# LEDS.net
KiCad netlist of a schematic drawn in Altium Designer
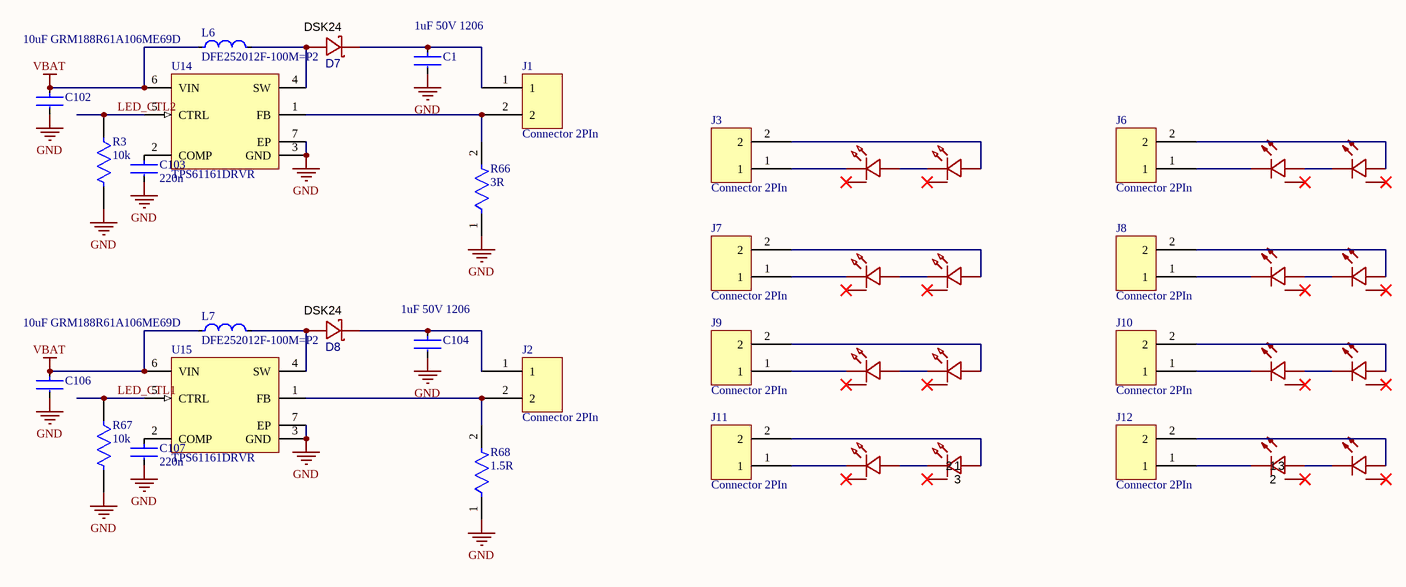
[diagram p0: LEDS.SchDoc]

(export (version "E")
  (design (tool "Eeschema 10.0.6"))
  (components
    (comp (ref "C1")
      (value "1uF 50V 1206")
      (footprint "FP-1206-L_3_2_0_2-W_1_6_0-IPC_B")
      (description "C1848")
      (fields (field (name "TOLERANCE") "5%"))
      (libsource (lib "LEAKCAM") (part "CMP-04427-010925-1"))
    )
    (comp (ref "C102")
      (value "10uF GRM188R61A106ME69D")
      (footprint "FP-GRM188-0_15-MFG")
      (description "C19702")
      (fields (field (name "TOLERANCE") "20%"))
      (libsource (lib "LEAKCAM") (part "CMP-06035-003612-1"))
    )
    (comp (ref "C103")
      (value "220n")
      (footprint "CAP_0402")
      (description "C16772")
      (fields (field (name "TOLERANCE") "10%"))
      (libsource (lib "LEAKCAM") (part "CMP-03422-001116-1"))
    )
    (comp (ref "C104")
      (value "1uF 50V 1206")
      (footprint "FP-1206-L_3_2_0_2-W_1_6_0-IPC_B")
      (description "C1848")
      (fields (field (name "TOLERANCE") "5%"))
      (libsource (lib "LEAKCAM") (part "CMP-04427-010925-1"))
    )
    (comp (ref "C106")
      (value "10uF GRM188R61A106ME69D")
      (footprint "FP-GRM188-0_15-MFG")
      (description "C19702")
      (fields (field (name "TOLERANCE") "20%"))
      (libsource (lib "LEAKCAM") (part "CMP-06035-003612-1"))
    )
    (comp (ref "C107")
      (value "220n")
      (footprint "CAP_0402")
      (description "C16772")
      (fields (field (name "TOLERANCE") "10%"))
      (libsource (lib "LEAKCAM") (part "CMP-03422-001116-1"))
    )
    (comp (ref "D7")
      (value "DSK24")
      (footprint "DSK24")
      (description "C22466352")
      (fields (field (name "MANUFACTURER") "MDD(辰达半导体)"))
      (libsource (lib "LEAKCAM") (part "dsk24_c64890"))
    )
    (comp (ref "D8")
      (value "DSK24")
      (footprint "DSK24")
      (description "C22466352")
      (fields (field (name "MANUFACTURER") "MDD(辰达半导体)"))
      (libsource (lib "LEAKCAM") (part "dsk24_c64890"))
    )
    (comp (ref "J1") (value "Connector 2PIn") (footprint "CON_2P") (libsource (lib "") (part "CON2P_1")))
    (comp (ref "J2") (value "Connector 2PIn") (footprint "CON_2P") (libsource (lib "") (part "CON2P_1")))
    (comp (ref "J3") (value "Connector 2PIn") (footprint "CON_2P") (libsource (lib "LEAKCAM") (part "CON2P")))
    (comp (ref "J6") (value "Connector 2PIn") (footprint "CON_2P") (libsource (lib "LEAKCAM") (part "CON2P")))
    (comp (ref "J7") (value "Connector 2PIn") (footprint "CON_2P") (libsource (lib "LEAKCAM") (part "CON2P")))
    (comp (ref "J8") (value "Connector 2PIn") (footprint "CON_2P") (libsource (lib "LEAKCAM") (part "CON2P")))
    (comp (ref "J9") (value "Connector 2PIn") (footprint "CON_2P") (libsource (lib "LEAKCAM") (part "CON2P")))
    (comp (ref "J10")
      (value "Connector 2PIn")
      (footprint "CON_2P")
      (libsource (lib "LEAKCAM") (part "CON2P"))
    )
    (comp (ref "J11")
      (value "Connector 2PIn")
      (footprint "CON_2P")
      (libsource (lib "LEAKCAM") (part "CON2P"))
    )
    (comp (ref "J12")
      (value "Connector 2PIn")
      (footprint "CON_2P")
      (libsource (lib "LEAKCAM") (part "CON2P"))
    )
    (comp (ref "L6")
      (value "DFE252012F-100M=P2")
      (footprint "FP-DFE252012C-IPC_B")
      (description "C703141")
      (fields (field (name "TOLERANCE") "20%"))
      (libsource (lib "LEAKCAM") (part "CMP-06042-007232-1"))
    )
    (comp (ref "L7")
      (value "DFE252012F-100M=P2")
      (footprint "FP-DFE252012C-IPC_B")
      (description "C703141")
      (fields (field (name "TOLERANCE") "20%"))
      (libsource (lib "LEAKCAM") (part "CMP-06042-007232-1"))
    )
    (comp (ref "LED1")
      (value "xl-hd3535uwc-a2")
      (footprint "XL-HD3535UWC-A2")
      (description "C3646951")
      (fields
        (field (name "MANUFACTURER") "XINGLIGHT(成兴光)")
        (field (name "MANUFACTURERPART") "XL-HD3535UWC-A2")
      )
      (libsource (lib "LEAKCAM") (part "xl-hd3535uwc-a2"))
    )
    (comp (ref "LED2")
      (value "xl-hd3535uwc-a2")
      (footprint "XL-HD3535UWC-A2")
      (description "C3646951")
      (fields
        (field (name "MANUFACTURER") "XINGLIGHT(成兴光)")
        (field (name "MANUFACTURERPART") "XL-HD3535UWC-A2")
      )
      (libsource (lib "LEAKCAM") (part "xl-hd3535uwc-a2"))
    )
    (comp (ref "LED3")
      (value "jnj-ltji0112w120/35mil/845-860nm")
      (footprint "JNJ-LTJI0112W120")
      (description "C19185834")
      (fields
        (field (name "MANUFACTURER") "JNJOPTO(强生光电)")
        (field (name "MANUFACTURERPART") "JNJ-LTJI0112W120/35mil/845-860nm")
      )
      (libsource (lib "LEAKCAM") (part "jnj-ltji0112w120/35mil/845-860nm"))
    )
    (comp (ref "LED4")
      (value "xl-hd3535uwc-a2")
      (footprint "XL-HD3535UWC-A2")
      (description "C3646951")
      (fields
        (field (name "MANUFACTURER") "XINGLIGHT(成兴光)")
        (field (name "MANUFACTURERPART") "XL-HD3535UWC-A2")
      )
      (libsource (lib "LEAKCAM") (part "xl-hd3535uwc-a2"))
    )
    (comp (ref "LED5")
      (value "xl-hd3535uwc-a2")
      (footprint "XL-HD3535UWC-A2")
      (description "C3646951")
      (fields
        (field (name "MANUFACTURER") "XINGLIGHT(成兴光)")
        (field (name "MANUFACTURERPART") "XL-HD3535UWC-A2")
      )
      (libsource (lib "LEAKCAM") (part "xl-hd3535uwc-a2"))
    )
    (comp (ref "LED6")
      (value "jnj-ltji0112w120/35mil/845-860nm")
      (footprint "JNJ-LTJI0112W120")
      (description "C19185834")
      (fields
        (field (name "MANUFACTURER") "JNJOPTO(强生光电)")
        (field (name "MANUFACTURERPART") "JNJ-LTJI0112W120/35mil/845-860nm")
      )
      (libsource (lib "LEAKCAM") (part "jnj-ltji0112w120/35mil/845-860nm"))
    )
    (comp (ref "LED7")
      (value "jnj-ltji0112w120/35mil/845-860nm")
      (footprint "JNJ-LTJI0112W120")
      (description "C19185834")
      (fields
        (field (name "MANUFACTURER") "JNJOPTO(强生光电)")
        (field (name "MANUFACTURERPART") "JNJ-LTJI0112W120/35mil/845-860nm")
      )
      (libsource (lib "LEAKCAM") (part "jnj-ltji0112w120/35mil/845-860nm"))
    )
    (comp (ref "LED8")
      (value "xl-hd3535uwc-a2")
      (footprint "XL-HD3535UWC-A2")
      (description "C3646951")
      (fields
        (field (name "MANUFACTURER") "XINGLIGHT(成兴光)")
        (field (name "MANUFACTURERPART") "XL-HD3535UWC-A2")
      )
      (libsource (lib "LEAKCAM") (part "xl-hd3535uwc-a2"))
    )
    (comp (ref "LED9")
      (value "xl-hd3535uwc-a2")
      (footprint "XL-HD3535UWC-A2")
      (description "C3646951")
      (fields
        (field (name "MANUFACTURER") "XINGLIGHT(成兴光)")
        (field (name "MANUFACTURERPART") "XL-HD3535UWC-A2")
      )
      (libsource (lib "LEAKCAM") (part "xl-hd3535uwc-a2"))
    )
    (comp (ref "LED10")
      (value "jnj-ltji0112w120/35mil/845-860nm")
      (footprint "JNJ-LTJI0112W120")
      (description "C19185834")
      (fields
        (field (name "MANUFACTURER") "JNJOPTO(强生光电)")
        (field (name "MANUFACTURERPART") "JNJ-LTJI0112W120/35mil/845-860nm")
      )
      (libsource (lib "LEAKCAM") (part "jnj-ltji0112w120/35mil/845-860nm"))
    )
    (comp (ref "LED11")
      (value "jnj-ltji0112w120/35mil/845-860nm")
      (footprint "JNJ-LTJI0112W120")
      (description "C19185834")
      (fields
        (field (name "MANUFACTURER") "JNJOPTO(强生光电)")
        (field (name "MANUFACTURERPART") "JNJ-LTJI0112W120/35mil/845-860nm")
      )
      (libsource (lib "LEAKCAM") (part "jnj-ltji0112w120/35mil/845-860nm"))
    )
    (comp (ref "LED12")
      (value "xl-hd3535uwc-a2")
      (footprint "XL-HD3535UWC-A2")
      (description "C3646951")
      (fields
        (field (name "MANUFACTURER") "XINGLIGHT(成兴光)")
        (field (name "MANUFACTURERPART") "XL-HD3535UWC-A2")
      )
      (libsource (lib "LEAKCAM") (part "xl-hd3535uwc-a2"))
    )
    (comp (ref "LED13")
      (value "xl-hd3535uwc-a2")
      (footprint "XL-HD3535UWC-A2")
      (description "C3646951")
      (fields
        (field (name "MANUFACTURER") "XINGLIGHT(成兴光)")
        (field (name "MANUFACTURERPART") "XL-HD3535UWC-A2")
      )
      (libsource (lib "") (part "xl-hd3535uwc-a2_1"))
    )
    (comp (ref "LED14")
      (value "jnj-ltji0112w120/35mil/845-860nm")
      (footprint "JNJ-LTJI0112W120")
      (description "C19185834")
      (fields
        (field (name "MANUFACTURER") "JNJOPTO(强生光电)")
        (field (name "MANUFACTURERPART") "JNJ-LTJI0112W120/35mil/845-860nm")
      )
      (libsource (lib "") (part "jnj-ltji0112w120/35mil/845-860nm_1"))
    )
    (comp (ref "LED15")
      (value "jnj-ltji0112w120/35mil/845-860nm")
      (footprint "JNJ-LTJI0112W120")
      (description "C19185834")
      (fields
        (field (name "MANUFACTURER") "JNJOPTO(强生光电)")
        (field (name "MANUFACTURERPART") "JNJ-LTJI0112W120/35mil/845-860nm")
      )
      (libsource (lib "LEAKCAM") (part "jnj-ltji0112w120/35mil/845-860nm"))
    )
    (comp (ref "LED16")
      (value "jnj-ltji0112w120/35mil/845-860nm")
      (footprint "JNJ-LTJI0112W120")
      (description "C19185834")
      (fields
        (field (name "MANUFACTURER") "JNJOPTO(强生光电)")
        (field (name "MANUFACTURERPART") "JNJ-LTJI0112W120/35mil/845-860nm")
      )
      (libsource (lib "LEAKCAM") (part "jnj-ltji0112w120/35mil/845-860nm"))
    )
    (comp (ref "R3")
      (value "10k")
      (footprint "RES_0402")
      (description "C25744")
      (fields (field (name "TOLERANCE") "1%"))
      (libsource (lib "") (part "CMP-03412-016018-1_1"))
    )
    (comp (ref "R66")
      (value "3R")
      (footprint "FP-SR0603-MFG")
      (description "C23157")
      (fields
        (field (name "MANUFACTURER PART NUMBER") "SR0603FR-7T10RL")
        (field (name "OCTOPART") "https://octopart.com/sr0603fr-7t10rl-yageo-91478074")
      )
      (libsource (lib "LEAKCAM") (part "CMP-03412-016018-1"))
    )
    (comp (ref "R67")
      (value "10k")
      (footprint "RES_0402")
      (description "C25744")
      (fields (field (name "TOLERANCE") "1%"))
      (libsource (lib "") (part "CMP-03412-016018-1_1"))
    )
    (comp (ref "R68")
      (value "1.5R")
      (footprint "FP-SR0603-MFG")
      (description "C22769")
      (fields
        (field (name "MANUFACTURER PART NUMBER") "SR0603FR-7T10RL")
        (field (name "OCTOPART") "https://octopart.com/sr0603fr-7t10rl-yageo-91478074")
      )
      (libsource (lib "LEAKCAM") (part "CMP-03412-016018-1"))
    )
    (comp (ref "U14")
      (value "TPS61161DRVR")
      (footprint "TPS61160ADRVT")
      (description "C324075")
      (fields (field (name "MANUFACTURER") "Texas Instruments"))
      (libsource (lib "LEAKCAM") (part "TI-TPS6116XDRV6-1600X1000TP"))
    )
    (comp (ref "U15")
      (value "TPS61161DRVR")
      (footprint "TPS61160ADRVT")
      (description "C324075")
      (fields (field (name "MANUFACTURER") "Texas Instruments"))
      (libsource (lib "LEAKCAM") (part "TI-TPS6116XDRV6-1600X1000TP"))
    )
  )
  (nets
    (net (code "1") (name "/LED_CTL1") (class "Default")
      (node (ref "R67") (pin "1") (pinfunction "1_1") (pintype "passive"))
      (node (ref "U15") (pin "5") (pinfunction "CTRL_5") (pintype "input"))
    )
    (net (code "2") (name "/LED_CTL2") (class "Default")
      (node (ref "R3") (pin "1") (pinfunction "1_1") (pintype "passive"))
      (node (ref "U14") (pin "5") (pinfunction "CTRL_5") (pintype "input"))
    )
    (net (code "3") (name "GND") (class "Default")
      (node (ref "C1") (pin "2") (pinfunction "2_2") (pintype "passive"))
      (node (ref "C102") (pin "2") (pinfunction "2_2") (pintype "passive"))
      (node (ref "C103") (pin "2") (pinfunction "2_2") (pintype "passive"))
      (node (ref "C104") (pin "2") (pinfunction "2_2") (pintype "passive"))
      (node (ref "C106") (pin "2") (pinfunction "2_2") (pintype "passive"))
      (node (ref "C107") (pin "2") (pinfunction "2_2") (pintype "passive"))
      (node (ref "R3") (pin "2") (pinfunction "2_2") (pintype "passive"))
      (node (ref "R66") (pin "1") (pinfunction "1_1") (pintype "passive"))
      (node (ref "R67") (pin "2") (pinfunction "2_2") (pintype "passive"))
      (node (ref "R68") (pin "1") (pinfunction "1_1") (pintype "passive"))
      (node (ref "U14") (pin "3") (pinfunction "GND_3") (pintype "power_in"))
      (node (ref "U14") (pin "7") (pinfunction "EP_7") (pintype "power_in"))
      (node (ref "U15") (pin "3") (pinfunction "GND_3") (pintype "power_in"))
      (node (ref "U15") (pin "7") (pinfunction "EP_7") (pintype "power_in"))
    )
    (net (code "4") (name "Net-(D7-A)") (class "Default")
      (node (ref "D7") (pin "2") (pinfunction "A_2") (pintype "passive"))
      (node (ref "L6") (pin "2") (pinfunction "2_2") (pintype "passive"))
      (node (ref "U14") (pin "4") (pinfunction "SW_4") (pintype "power_in"))
    )
    (net (code "5") (name "Net-(D7-K)") (class "Default")
      (node (ref "C1") (pin "1") (pinfunction "1_1") (pintype "passive"))
      (node (ref "D7") (pin "1") (pinfunction "K_1") (pintype "passive"))
      (node (ref "J1") (pin "1") (pinfunction "1_1") (pintype "passive"))
    )
    (net (code "6") (name "Net-(D8-A)") (class "Default")
      (node (ref "D8") (pin "2") (pinfunction "A_2") (pintype "passive"))
      (node (ref "L7") (pin "2") (pinfunction "2_2") (pintype "passive"))
      (node (ref "U15") (pin "4") (pinfunction "SW_4") (pintype "power_in"))
    )
    (net (code "7") (name "Net-(D8-K)") (class "Default")
      (node (ref "C104") (pin "1") (pinfunction "1_1") (pintype "passive"))
      (node (ref "D8") (pin "1") (pinfunction "K_1") (pintype "passive"))
      (node (ref "J2") (pin "1") (pinfunction "1_1") (pintype "passive"))
    )
    (net (code "8") (name "Net-(J3-Pad1)") (class "Default")
      (node (ref "J3") (pin "1") (pinfunction "1_1") (pintype "passive"))
      (node (ref "LED1") (pin "1") (pinfunction "1_1") (pintype "passive"))
    )
    (net (code "9") (name "Net-(J3-Pad2)") (class "Default")
      (node (ref "J3") (pin "2") (pinfunction "2_2") (pintype "passive"))
      (node (ref "LED2") (pin "2") (pinfunction "2_2") (pintype "passive"))
    )
    (net (code "10") (name "Net-(J6-Pad1)") (class "Default")
      (node (ref "J6") (pin "1") (pinfunction "1_1") (pintype "passive"))
      (node (ref "LED16") (pin "3") (pinfunction "3_3") (pintype "passive"))
    )
    (net (code "11") (name "Net-(J6-Pad2)") (class "Default")
      (node (ref "J6") (pin "2") (pinfunction "2_2") (pintype "passive"))
      (node (ref "LED3") (pin "1") (pinfunction "1_1") (pintype "passive"))
    )
    (net (code "12") (name "Net-(J7-Pad1)") (class "Default")
      (node (ref "J7") (pin "1") (pinfunction "1_1") (pintype "passive"))
      (node (ref "LED4") (pin "1") (pinfunction "1_1") (pintype "passive"))
    )
    (net (code "13") (name "Net-(J7-Pad2)") (class "Default")
      (node (ref "J7") (pin "2") (pinfunction "2_2") (pintype "passive"))
      (node (ref "LED5") (pin "2") (pinfunction "2_2") (pintype "passive"))
    )
    (net (code "14") (name "Net-(J8-Pad1)") (class "Default")
      (node (ref "J8") (pin "1") (pinfunction "1_1") (pintype "passive"))
      (node (ref "LED6") (pin "3") (pinfunction "3_3") (pintype "passive"))
    )
    (net (code "15") (name "Net-(J8-Pad2)") (class "Default")
      (node (ref "J8") (pin "2") (pinfunction "2_2") (pintype "passive"))
      (node (ref "LED7") (pin "1") (pinfunction "1_1") (pintype "passive"))
    )
    (net (code "16") (name "Net-(J9-Pad1)") (class "Default")
      (node (ref "J9") (pin "1") (pinfunction "1_1") (pintype "passive"))
      (node (ref "LED8") (pin "1") (pinfunction "1_1") (pintype "passive"))
    )
    (net (code "17") (name "Net-(J9-Pad2)") (class "Default")
      (node (ref "J9") (pin "2") (pinfunction "2_2") (pintype "passive"))
      (node (ref "LED9") (pin "2") (pinfunction "2_2") (pintype "passive"))
    )
    (net (code "18") (name "Net-(J10-Pad1)") (class "Default")
      (node (ref "J10") (pin "1") (pinfunction "1_1") (pintype "passive"))
      (node (ref "LED10") (pin "3") (pinfunction "3_3") (pintype "passive"))
    )
    (net (code "19") (name "Net-(J10-Pad2)") (class "Default")
      (node (ref "J10") (pin "2") (pinfunction "2_2") (pintype "passive"))
      (node (ref "LED11") (pin "1") (pinfunction "1_1") (pintype "passive"))
    )
    (net (code "20") (name "Net-(J11-Pad1)") (class "Default")
      (node (ref "J11") (pin "1") (pinfunction "1_1") (pintype "passive"))
      (node (ref "LED12") (pin "1") (pinfunction "1_1") (pintype "passive"))
    )
    (net (code "21") (name "Net-(J11-Pad2)") (class "Default")
      (node (ref "J11") (pin "2") (pinfunction "2_2") (pintype "passive"))
      (node (ref "LED13") (pin "2") (pinfunction "2_2") (pintype "passive"))
    )
    (net (code "22") (name "Net-(J12-Pad1)") (class "Default")
      (node (ref "J12") (pin "1") (pinfunction "1_1") (pintype "passive"))
      (node (ref "LED14") (pin "3") (pinfunction "3_3") (pintype "passive"))
    )
    (net (code "23") (name "Net-(J12-Pad2)") (class "Default")
      (node (ref "J12") (pin "2") (pinfunction "2_2") (pintype "passive"))
      (node (ref "LED15") (pin "1") (pinfunction "1_1") (pintype "passive"))
    )
    (net (code "24") (name "Net-(LED1-Pad2)") (class "Default")
      (node (ref "LED1") (pin "2") (pinfunction "2_2") (pintype "passive"))
      (node (ref "LED2") (pin "1") (pinfunction "1_1") (pintype "passive"))
    )
    (net (code "25") (name "Net-(LED4-Pad2)") (class "Default")
      (node (ref "LED4") (pin "2") (pinfunction "2_2") (pintype "passive"))
      (node (ref "LED5") (pin "1") (pinfunction "1_1") (pintype "passive"))
    )
    (net (code "26") (name "Net-(LED6-Pad1)") (class "Default")
      (node (ref "LED6") (pin "1") (pinfunction "1_1") (pintype "passive"))
      (node (ref "LED7") (pin "3") (pinfunction "3_3") (pintype "passive"))
    )
    (net (code "27") (name "Net-(LED8-Pad2)") (class "Default")
      (node (ref "LED8") (pin "2") (pinfunction "2_2") (pintype "passive"))
      (node (ref "LED9") (pin "1") (pinfunction "1_1") (pintype "passive"))
    )
    (net (code "28") (name "Net-(LED10-Pad1)") (class "Default")
      (node (ref "LED10") (pin "1") (pinfunction "1_1") (pintype "passive"))
      (node (ref "LED11") (pin "3") (pinfunction "3_3") (pintype "passive"))
    )
    (net (code "29") (name "Net-(LED12-Pad2)") (class "Default")
      (node (ref "LED12") (pin "2") (pinfunction "2_2") (pintype "passive"))
      (node (ref "LED13") (pin "1") (pinfunction "1_1") (pintype "passive"))
    )
    (net (code "30") (name "Net-(LED14-Pad1)") (class "Default")
      (node (ref "LED14") (pin "1") (pinfunction "1_1") (pintype "passive"))
      (node (ref "LED15") (pin "3") (pinfunction "3_3") (pintype "passive"))
    )
    (net (code "31") (name "Net-(LED16-Pad1)") (class "Default")
      (node (ref "LED16") (pin "1") (pinfunction "1_1") (pintype "passive"))
      (node (ref "LED3") (pin "3") (pinfunction "3_3") (pintype "passive"))
    )
    (net (code "32") (name "Net-(U14-COMP)") (class "Default")
      (node (ref "C103") (pin "1") (pinfunction "1_1") (pintype "passive"))
      (node (ref "U14") (pin "2") (pinfunction "COMP_2") (pintype "passive"))
    )
    (net (code "33") (name "Net-(U14-FB)") (class "Default")
      (node (ref "J1") (pin "2") (pinfunction "2_2") (pintype "passive"))
      (node (ref "R66") (pin "2") (pinfunction "2_2") (pintype "passive"))
      (node (ref "U14") (pin "1") (pinfunction "FB_1") (pintype "passive"))
    )
    (net (code "34") (name "Net-(U15-COMP)") (class "Default")
      (node (ref "C107") (pin "1") (pinfunction "1_1") (pintype "passive"))
      (node (ref "U15") (pin "2") (pinfunction "COMP_2") (pintype "passive"))
    )
    (net (code "35") (name "Net-(U15-FB)") (class "Default")
      (node (ref "J2") (pin "2") (pinfunction "2_2") (pintype "passive"))
      (node (ref "R68") (pin "2") (pinfunction "2_2") (pintype "passive"))
      (node (ref "U15") (pin "1") (pinfunction "FB_1") (pintype "passive"))
    )
    (net (code "36") (name "VBAT") (class "Default")
      (node (ref "C102") (pin "1") (pinfunction "1_1") (pintype "passive"))
      (node (ref "C106") (pin "1") (pinfunction "1_1") (pintype "passive"))
      (node (ref "L6") (pin "1") (pinfunction "1_1") (pintype "passive"))
      (node (ref "L7") (pin "1") (pinfunction "1_1") (pintype "passive"))
      (node (ref "U14") (pin "6") (pinfunction "VIN_6") (pintype "power_in"))
      (node (ref "U15") (pin "6") (pinfunction "VIN_6") (pintype "power_in"))
    )
    (net (code "37") (name "unconnected-(LED1-Pad3)") (class "Default")
      (node (ref "LED1") (pin "3") (pinfunction "3_3") (pintype "passive+no_connect"))
    )
    (net (code "38") (name "unconnected-(LED2-Pad3)") (class "Default")
      (node (ref "LED2") (pin "3") (pinfunction "3_3") (pintype "passive+no_connect"))
    )
    (net (code "39") (name "unconnected-(LED3-Pad2)") (class "Default")
      (node (ref "LED3") (pin "2") (pinfunction "2_2") (pintype "passive+no_connect"))
    )
    (net (code "40") (name "unconnected-(LED4-Pad3)") (class "Default")
      (node (ref "LED4") (pin "3") (pinfunction "3_3") (pintype "passive+no_connect"))
    )
    (net (code "41") (name "unconnected-(LED5-Pad3)") (class "Default")
      (node (ref "LED5") (pin "3") (pinfunction "3_3") (pintype "passive+no_connect"))
    )
    (net (code "42") (name "unconnected-(LED6-Pad2)") (class "Default")
      (node (ref "LED6") (pin "2") (pinfunction "2_2") (pintype "passive+no_connect"))
    )
    (net (code "43") (name "unconnected-(LED7-Pad2)") (class "Default")
      (node (ref "LED7") (pin "2") (pinfunction "2_2") (pintype "passive+no_connect"))
    )
    (net (code "44") (name "unconnected-(LED8-Pad3)") (class "Default")
      (node (ref "LED8") (pin "3") (pinfunction "3_3") (pintype "passive+no_connect"))
    )
    (net (code "45") (name "unconnected-(LED9-Pad3)") (class "Default")
      (node (ref "LED9") (pin "3") (pinfunction "3_3") (pintype "passive+no_connect"))
    )
    (net (code "46") (name "unconnected-(LED10-Pad2)") (class "Default")
      (node (ref "LED10") (pin "2") (pinfunction "2_2") (pintype "passive+no_connect"))
    )
    (net (code "47") (name "unconnected-(LED11-Pad2)") (class "Default")
      (node (ref "LED11") (pin "2") (pinfunction "2_2") (pintype "passive+no_connect"))
    )
    (net (code "48") (name "unconnected-(LED12-Pad3)") (class "Default")
      (node (ref "LED12") (pin "3") (pinfunction "3_3") (pintype "passive+no_connect"))
    )
    (net (code "49") (name "unconnected-(LED13-Pad3)") (class "Default")
      (node (ref "LED13") (pin "3") (pinfunction "3_3") (pintype "passive+no_connect"))
    )
    (net (code "50") (name "unconnected-(LED14-Pad2)") (class "Default")
      (node (ref "LED14") (pin "2") (pinfunction "2_2") (pintype "passive+no_connect"))
    )
    (net (code "51") (name "unconnected-(LED15-Pad2)") (class "Default")
      (node (ref "LED15") (pin "2") (pinfunction "2_2") (pintype "passive+no_connect"))
    )
    (net (code "52") (name "unconnected-(LED16-Pad2)") (class "Default")
      (node (ref "LED16") (pin "2") (pinfunction "2_2") (pintype "passive+no_connect"))
    )
  )
)
